# sheet.net
KiCad netlist of a schematic drawn in EasyEDA
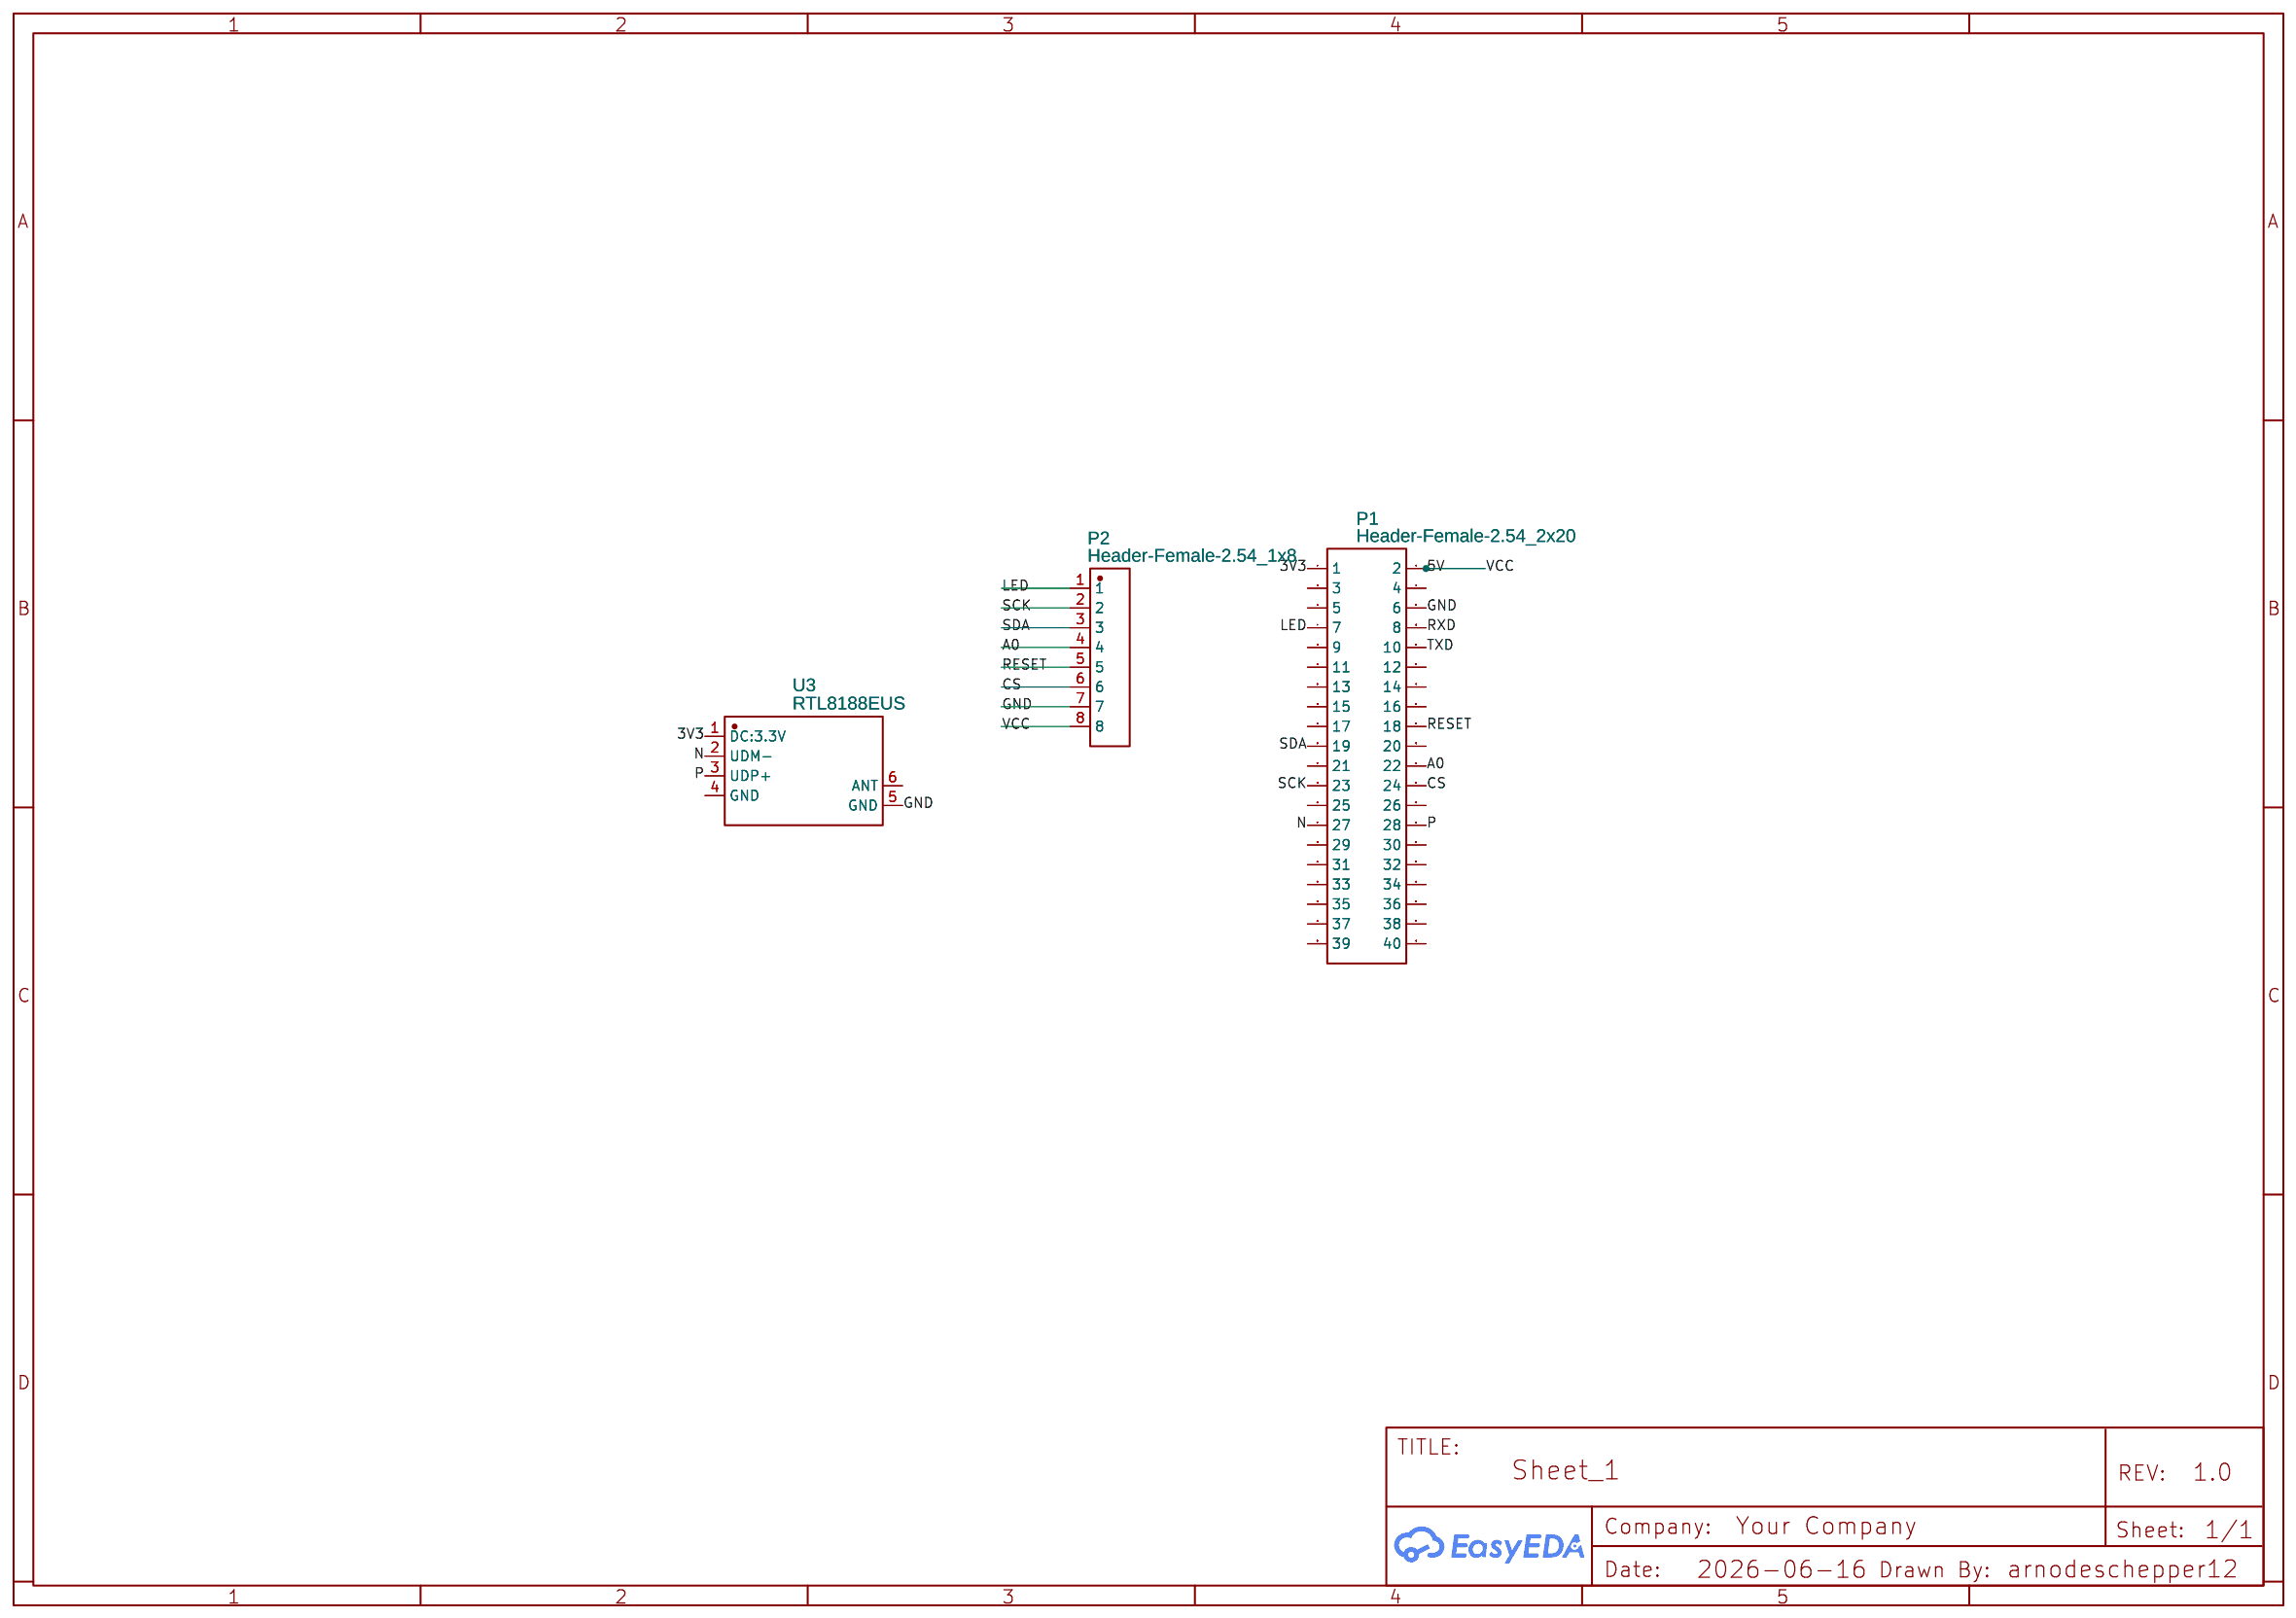
[diagram p0: schematic sheet]

(export (version "E")
  (design (tool "Eeschema 10.0.6"))
  (components
    (comp (ref "P1")
      (value "Header-Female-2.54_2x20")
      (fields (field (name "Manufacturer Part") "2.54-2*20P母") (field (name "Manufacturer") "BOOMELE(博穆精密)"))
      (libsource (lib "") (part "Header-Female-2.54_2x20"))
    )
    (comp (ref "P2")
      (value "Header-Female-2.54_1x8")
      (fields (field (name "Manufacturer Part") "2.54-1*8P母环保") (field (name "Manufacturer") "BOOMELE(博穆精密)"))
      (libsource (lib "") (part "Header-Female-2.54_1x8"))
    )
    (comp (ref "U3") (value "RTL8188EUS") (libsource (lib "") (part "RTL8188EUS")))
  )
  (nets
    (net (code "1") (name "/3V3") (class "Default")
      (node (ref "P1") (pin "1") (pinfunction "1_1") (pintype "input"))
      (node (ref "U3") (pin "1") (pinfunction "DC:3.3V_1") (pintype "unspecified"))
    )
    (net (code "2") (name "/5V") (class "Default")
      (node (ref "P1") (pin "2") (pinfunction "2_2") (pintype "input"))
      (node (ref "P2") (pin "8") (pinfunction "8_8") (pintype "unspecified"))
    )
    (net (code "3") (name "/A0") (class "Default")
      (node (ref "P1") (pin "22") (pinfunction "22_22") (pintype "input"))
      (node (ref "P2") (pin "4") (pinfunction "4_4") (pintype "unspecified"))
    )
    (net (code "4") (name "/CS") (class "Default")
      (node (ref "P1") (pin "24") (pinfunction "24_24") (pintype "input"))
      (node (ref "P2") (pin "6") (pinfunction "6_6") (pintype "unspecified"))
    )
    (net (code "5") (name "/GND") (class "Default")
      (node (ref "P1") (pin "6") (pinfunction "6_6") (pintype "input"))
      (node (ref "P2") (pin "7") (pinfunction "7_7") (pintype "unspecified"))
      (node (ref "U3") (pin "5") (pinfunction "GND_5") (pintype "unspecified"))
    )
    (net (code "6") (name "/LED") (class "Default")
      (node (ref "P1") (pin "7") (pinfunction "7_7") (pintype "input"))
      (node (ref "P2") (pin "1") (pinfunction "1_1") (pintype "unspecified"))
    )
    (net (code "7") (name "/N") (class "Default")
      (node (ref "P1") (pin "27") (pinfunction "27_27") (pintype "input"))
      (node (ref "U3") (pin "2") (pinfunction "UDM-_2") (pintype "unspecified"))
    )
    (net (code "8") (name "/P") (class "Default")
      (node (ref "P1") (pin "28") (pinfunction "28_28") (pintype "input"))
      (node (ref "U3") (pin "3") (pinfunction "UDP+_3") (pintype "unspecified"))
    )
    (net (code "9") (name "/RESET") (class "Default")
      (node (ref "P1") (pin "18") (pinfunction "18_18") (pintype "input"))
      (node (ref "P2") (pin "5") (pinfunction "5_5") (pintype "unspecified"))
    )
    (net (code "10") (name "/RXD") (class "Default")
      (node (ref "P1") (pin "8") (pinfunction "8_8") (pintype "input"))
    )
    (net (code "11") (name "/SCK") (class "Default")
      (node (ref "P1") (pin "23") (pinfunction "23_23") (pintype "input"))
      (node (ref "P2") (pin "2") (pinfunction "2_2") (pintype "unspecified"))
    )
    (net (code "12") (name "/SDA") (class "Default")
      (node (ref "P1") (pin "19") (pinfunction "19_19") (pintype "input"))
      (node (ref "P2") (pin "3") (pinfunction "3_3") (pintype "unspecified"))
    )
    (net (code "13") (name "/TXD") (class "Default")
      (node (ref "P1") (pin "10") (pinfunction "10_10") (pintype "input"))
    )
    (net (code "14") (name "unconnected-(P1-Pad3)") (class "Default")
      (node (ref "P1") (pin "3") (pinfunction "3_3") (pintype "input"))
    )
    (net (code "15") (name "unconnected-(P1-Pad4)") (class "Default")
      (node (ref "P1") (pin "4") (pinfunction "4_4") (pintype "input"))
    )
    (net (code "16") (name "unconnected-(P1-Pad5)") (class "Default")
      (node (ref "P1") (pin "5") (pinfunction "5_5") (pintype "input"))
    )
    (net (code "17") (name "unconnected-(P1-Pad9)") (class "Default")
      (node (ref "P1") (pin "9") (pinfunction "9_9") (pintype "input"))
    )
    (net (code "18") (name "unconnected-(P1-Pad11)") (class "Default")
      (node (ref "P1") (pin "11") (pinfunction "11_11") (pintype "input"))
    )
    (net (code "19") (name "unconnected-(P1-Pad12)") (class "Default")
      (node (ref "P1") (pin "12") (pinfunction "12_12") (pintype "input"))
    )
    (net (code "20") (name "unconnected-(P1-Pad13)") (class "Default")
      (node (ref "P1") (pin "13") (pinfunction "13_13") (pintype "input"))
    )
    (net (code "21") (name "unconnected-(P1-Pad14)") (class "Default")
      (node (ref "P1") (pin "14") (pinfunction "14_14") (pintype "input"))
    )
    (net (code "22") (name "unconnected-(P1-Pad15)") (class "Default")
      (node (ref "P1") (pin "15") (pinfunction "15_15") (pintype "input"))
    )
    (net (code "23") (name "unconnected-(P1-Pad16)") (class "Default")
      (node (ref "P1") (pin "16") (pinfunction "16_16") (pintype "input"))
    )
    (net (code "24") (name "unconnected-(P1-Pad17)") (class "Default")
      (node (ref "P1") (pin "17") (pinfunction "17_17") (pintype "input"))
    )
    (net (code "25") (name "unconnected-(P1-Pad20)") (class "Default")
      (node (ref "P1") (pin "20") (pinfunction "20_20") (pintype "input"))
    )
    (net (code "26") (name "unconnected-(P1-Pad21)") (class "Default")
      (node (ref "P1") (pin "21") (pinfunction "21_21") (pintype "input"))
    )
    (net (code "27") (name "unconnected-(P1-Pad25)") (class "Default")
      (node (ref "P1") (pin "25") (pinfunction "25_25") (pintype "input"))
    )
    (net (code "28") (name "unconnected-(P1-Pad26)") (class "Default")
      (node (ref "P1") (pin "26") (pinfunction "26_26") (pintype "input"))
    )
    (net (code "29") (name "unconnected-(P1-Pad29)") (class "Default")
      (node (ref "P1") (pin "29") (pinfunction "29_29") (pintype "input"))
    )
    (net (code "30") (name "unconnected-(P1-Pad30)") (class "Default")
      (node (ref "P1") (pin "30") (pinfunction "30_30") (pintype "input"))
    )
    (net (code "31") (name "unconnected-(P1-Pad31)") (class "Default")
      (node (ref "P1") (pin "31") (pinfunction "31_31") (pintype "input"))
    )
    (net (code "32") (name "unconnected-(P1-Pad32)") (class "Default")
      (node (ref "P1") (pin "32") (pinfunction "32_32") (pintype "input"))
    )
    (net (code "33") (name "unconnected-(P1-Pad33)") (class "Default")
      (node (ref "P1") (pin "33") (pinfunction "33_33") (pintype "input"))
    )
    (net (code "34") (name "unconnected-(P1-Pad34)") (class "Default")
      (node (ref "P1") (pin "34") (pinfunction "34_34") (pintype "input"))
    )
    (net (code "35") (name "unconnected-(P1-Pad35)") (class "Default")
      (node (ref "P1") (pin "35") (pinfunction "35_35") (pintype "input"))
    )
    (net (code "36") (name "unconnected-(P1-Pad36)") (class "Default")
      (node (ref "P1") (pin "36") (pinfunction "36_36") (pintype "input"))
    )
    (net (code "37") (name "unconnected-(P1-Pad37)") (class "Default")
      (node (ref "P1") (pin "37") (pinfunction "37_37") (pintype "input"))
    )
    (net (code "38") (name "unconnected-(P1-Pad38)") (class "Default")
      (node (ref "P1") (pin "38") (pinfunction "38_38") (pintype "input"))
    )
    (net (code "39") (name "unconnected-(P1-Pad39)") (class "Default")
      (node (ref "P1") (pin "39") (pinfunction "39_39") (pintype "input"))
    )
    (net (code "40") (name "unconnected-(P1-Pad40)") (class "Default")
      (node (ref "P1") (pin "40") (pinfunction "40_40") (pintype "input"))
    )
    (net (code "41") (name "unconnected-(U3-ANT-Pad6)") (class "Default")
      (node (ref "U3") (pin "6") (pinfunction "ANT_6") (pintype "unspecified"))
    )
    (net (code "42") (name "unconnected-(U3-GND-Pad4)") (class "Default")
      (node (ref "U3") (pin "4") (pinfunction "GND_4") (pintype "unspecified"))
    )
  )
)
